# rld-node.net
KiCad netlist of a schematic drawn in EAGLE
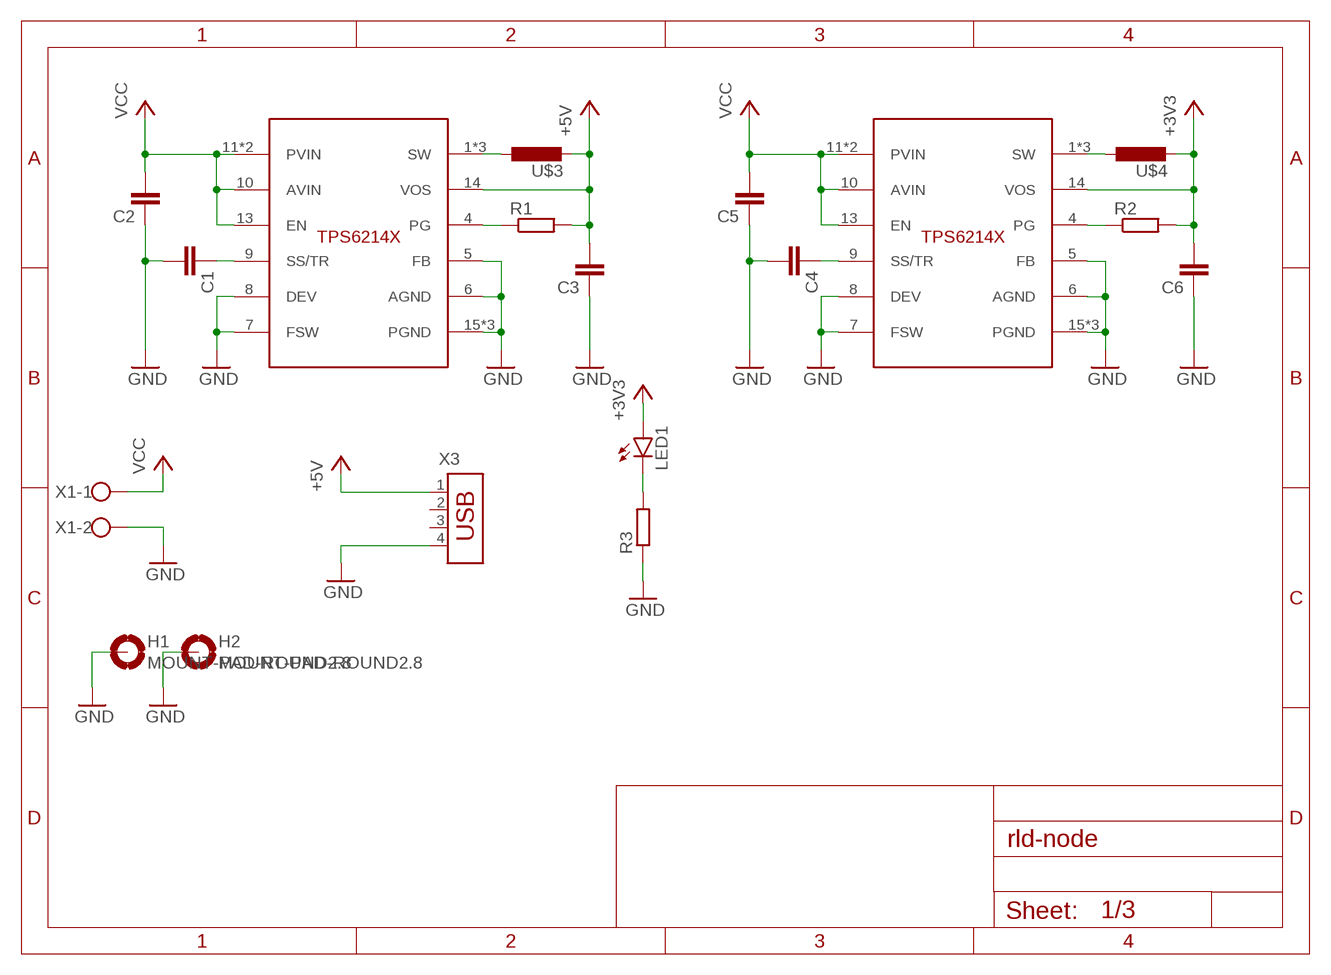
[diagram p0: schematic, sheet 1]
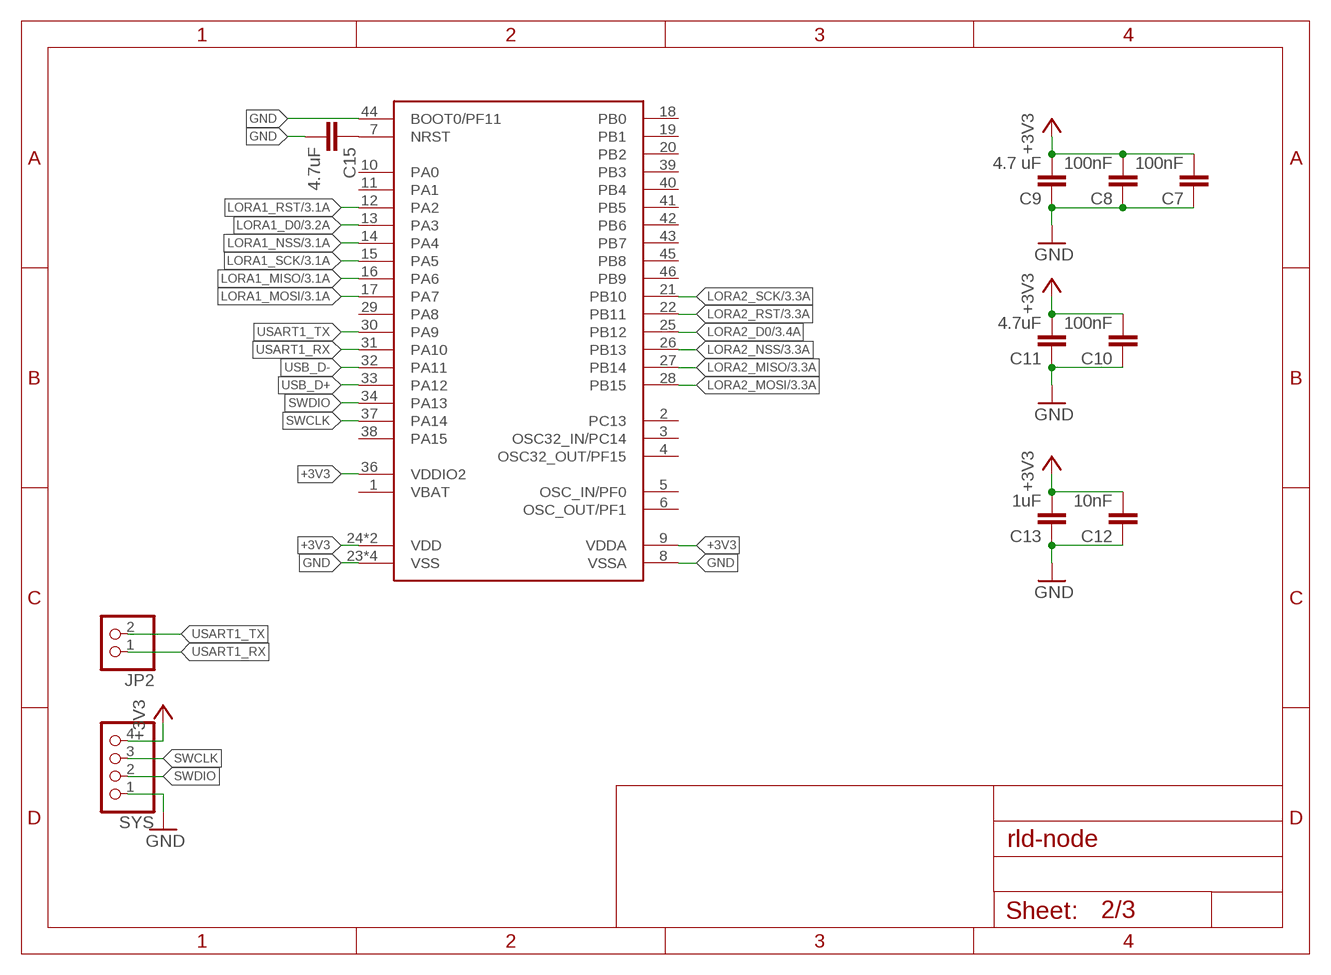
[diagram p1: schematic, sheet 2]
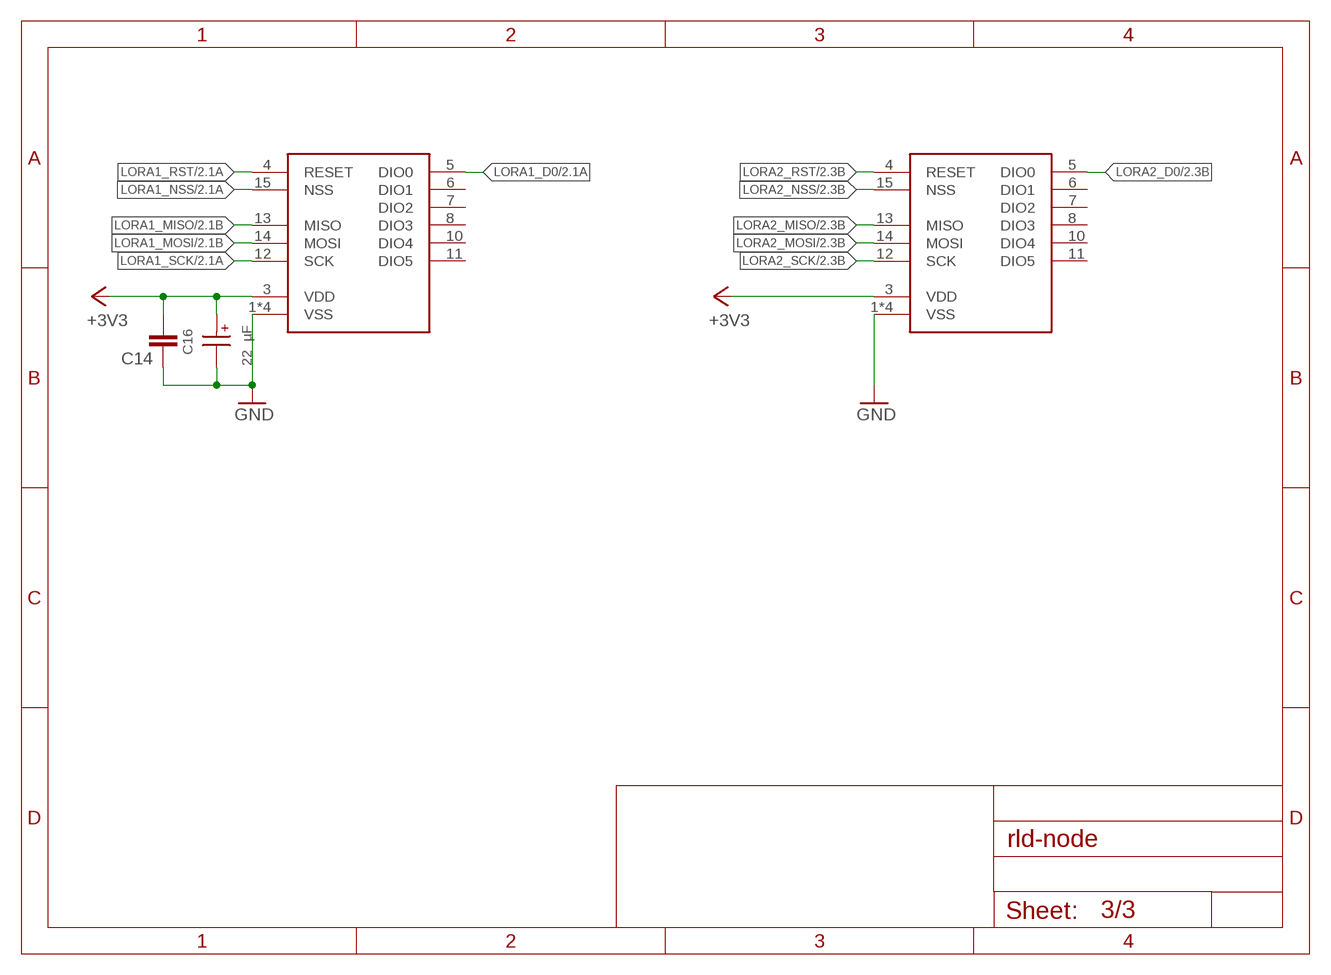
[diagram p2: schematic, sheet 3]

(export (version "E")
  (design (tool "Eeschema 10.0.6"))
  (components
    (comp (ref "C1")
      (value "C-EUC0805")
      (footprint "eagle-import:C0805")
      (libsource (lib "eagle-import") (part "C-EUC0805"))
    )
    (comp (ref "C2")
      (value "C-EUC0805")
      (footprint "eagle-import:C0805")
      (libsource (lib "eagle-import") (part "C-EUC0805"))
    )
    (comp (ref "C3")
      (value "C-EUC0805")
      (footprint "eagle-import:C0805")
      (libsource (lib "eagle-import") (part "C-EUC0805"))
    )
    (comp (ref "C4")
      (value "C-EUC0805")
      (footprint "eagle-import:C0805")
      (libsource (lib "eagle-import") (part "C-EUC0805"))
    )
    (comp (ref "C5")
      (value "C-EUC0805")
      (footprint "eagle-import:C0805")
      (libsource (lib "eagle-import") (part "C-EUC0805"))
    )
    (comp (ref "C6")
      (value "C-EUC0805")
      (footprint "eagle-import:C0805")
      (libsource (lib "eagle-import") (part "C-EUC0805"))
    )
    (comp (ref "H1")
      (value "MOUNT-PAD-ROUND2.8")
      (footprint "eagle-import:2,8-PAD")
      (libsource (lib "eagle-import") (part "MOUNT-PAD-ROUND2.8"))
    )
    (comp (ref "H2")
      (value "MOUNT-PAD-ROUND2.8")
      (footprint "eagle-import:2,8-PAD")
      (libsource (lib "eagle-import") (part "MOUNT-PAD-ROUND2.8"))
    )
    (comp (ref "L1")
      (value "TPS6214X")
      (footprint "eagle-import:VQFN16-3X3")
      (libsource (lib "eagle-import") (part "TPS6214X"))
    )
    (comp (ref "L2")
      (value "TPS6214X")
      (footprint "eagle-import:VQFN16-3X3")
      (libsource (lib "eagle-import") (part "TPS6214X"))
    )
    (comp (ref "LED1")
      (value "LEDSML0805")
      (footprint "eagle-import:SML0805")
      (libsource (lib "eagle-import") (part "LEDSML0805"))
    )
    (comp (ref "R1")
      (value "R-EU_R0805")
      (footprint "eagle-import:R0805")
      (libsource (lib "eagle-import") (part "R-EU_R0805"))
    )
    (comp (ref "R2")
      (value "R-EU_R0805")
      (footprint "eagle-import:R0805")
      (libsource (lib "eagle-import") (part "R-EU_R0805"))
    )
    (comp (ref "R3")
      (value "R-EU_R0805")
      (footprint "eagle-import:R0805")
      (libsource (lib "eagle-import") (part "R-EU_R0805"))
    )
    (comp (ref "U$3")
      (value "IHLP-1212")
      (footprint "eagle-import:1212BZ")
      (libsource (lib "eagle-import") (part "IHLP-1212"))
    )
    (comp (ref "U$4")
      (value "IHLP-1212")
      (footprint "eagle-import:1212BZ")
      (libsource (lib "eagle-import") (part "IHLP-1212"))
    )
    (comp (ref "X1")
      (value "W237-102")
      (footprint "eagle-import:W237-102")
      (fields (field (name "MPN") "237-102"))
      (libsource (lib "eagle-import") (part "W237-102"))
    )
    (comp (ref "X3")
      (value "USB-787616")
      (footprint "eagle-import:USB")
      (libsource (lib "eagle-import") (part "USB-787616"))
    )
    (comp (ref "C7")
      (value "100nF")
      (footprint "eagle-import:C0805")
      (libsource (lib "eagle-import") (part "C-EUC0805"))
    )
    (comp (ref "C8")
      (value "100nF")
      (footprint "eagle-import:C0805")
      (libsource (lib "eagle-import") (part "C-EUC0805"))
    )
    (comp (ref "C9")
      (value "4.7 uF")
      (footprint "eagle-import:C0805")
      (libsource (lib "eagle-import") (part "C-EUC0805"))
    )
    (comp (ref "C10")
      (value "100nF")
      (footprint "eagle-import:C0805")
      (libsource (lib "eagle-import") (part "C-EUC0805"))
    )
    (comp (ref "C11")
      (value "4.7uF")
      (footprint "eagle-import:C0805")
      (libsource (lib "eagle-import") (part "C-EUC0805"))
    )
    (comp (ref "C12")
      (value "10nF")
      (footprint "eagle-import:C0805")
      (libsource (lib "eagle-import") (part "C-EUC0805"))
    )
    (comp (ref "C13")
      (value "1uF")
      (footprint "eagle-import:C0805")
      (libsource (lib "eagle-import") (part "C-EUC0805"))
    )
    (comp (ref "C15")
      (value "4.7uF")
      (footprint "eagle-import:C0805")
      (libsource (lib "eagle-import") (part "C-EUC0805"))
    )
    (comp (ref "JP2")
      (value "PINHD-1X2")
      (footprint "eagle-import:1X02")
      (libsource (lib "eagle-import") (part "PINHD-1X2"))
    )
    (comp (ref "SYS")
      (value "PINHD-1X4")
      (footprint "eagle-import:1X04")
      (libsource (lib "eagle-import") (part "PINHD-1X4"))
    )
    (comp (ref "U$5")
      (value "STM32-F042X4/6-48")
      (footprint "eagle-import:UFQFPN48-7X7")
      (libsource (lib "eagle-import") (part "STM32-F042X4/6-48"))
    )
    (comp (ref "C14")
      (value "C-EUC0805")
      (footprint "eagle-import:C0805")
      (libsource (lib "eagle-import") (part "C-EUC0805"))
    )
    (comp (ref "C16")
      (value "22 µF")
      (footprint "eagle-import:WCAP-ASLI_4X5.5(DXL)")
      (libsource (lib "eagle-import") (part "WCAP-ASLI_4X5.5_865080340003"))
    )
    (comp (ref "U$6")
      (value "RA-02")
      (footprint "eagle-import:RA-01_RA-02")
      (libsource (lib "eagle-import") (part "RA-02"))
    )
    (comp (ref "U$7")
      (value "RA-02")
      (footprint "eagle-import:RA-01_RA-02")
      (libsource (lib "eagle-import") (part "RA-02"))
    )
  )
  (nets
    (net (code "1") (name "+3V3") (class "Default")
      (node (ref "C10") (pin "2") (pinfunction "2_2") (pintype "passive"))
      (node (ref "C11") (pin "2") (pinfunction "2_2") (pintype "passive"))
      (node (ref "C12") (pin "2") (pinfunction "2_2") (pintype "passive"))
      (node (ref "C13") (pin "2") (pinfunction "2_2") (pintype "passive"))
      (node (ref "C14") (pin "2") (pinfunction "2_2") (pintype "passive"))
      (node (ref "C16") (pin "1") (pinfunction "+_1") (pintype "passive"))
      (node (ref "C6") (pin "2") (pinfunction "2_2") (pintype "passive"))
      (node (ref "C7") (pin "2") (pinfunction "2_2") (pintype "passive"))
      (node (ref "C8") (pin "2") (pinfunction "2_2") (pintype "passive"))
      (node (ref "C9") (pin "2") (pinfunction "2_2") (pintype "passive"))
      (node (ref "L2") (pin "14") (pinfunction "VOS_14") (pintype "bidirectional"))
      (node (ref "LED1") (pin "A") (pinfunction "A_A") (pintype "passive"))
      (node (ref "R2") (pin "2") (pinfunction "2_2") (pintype "passive"))
      (node (ref "SYS") (pin "4") (pinfunction "4_4") (pintype "passive"))
      (node (ref "U$4") (pin "2") (pinfunction "2_2") (pintype "passive"))
      (node (ref "U$5") (pin "24") (pinfunction "VDD_24") (pintype "bidirectional"))
      (node (ref "U$5") (pin "36") (pinfunction "VDDIO2_36") (pintype "bidirectional"))
      (node (ref "U$5") (pin "48") (pinfunction "VDD_48") (pintype "bidirectional"))
      (node (ref "U$5") (pin "9") (pinfunction "VDDA_9") (pintype "bidirectional"))
      (node (ref "U$6") (pin "3") (pinfunction "VDD_3") (pintype "bidirectional"))
      (node (ref "U$7") (pin "3") (pinfunction "VDD_3") (pintype "bidirectional"))
    )
    (net (code "2") (name "+5V") (class "Default")
      (node (ref "C3") (pin "2") (pinfunction "2_2") (pintype "passive"))
      (node (ref "L1") (pin "14") (pinfunction "VOS_14") (pintype "bidirectional"))
      (node (ref "R1") (pin "2") (pinfunction "2_2") (pintype "passive"))
      (node (ref "U$3") (pin "2") (pinfunction "2_2") (pintype "passive"))
      (node (ref "X3") (pin "1") (pinfunction "1_1") (pintype "passive"))
    )
    (net (code "3") (name "GND") (class "Default")
      (node (ref "C1") (pin "2") (pinfunction "2_2") (pintype "passive"))
      (node (ref "C10") (pin "1") (pinfunction "1_1") (pintype "passive"))
      (node (ref "C11") (pin "1") (pinfunction "1_1") (pintype "passive"))
      (node (ref "C12") (pin "1") (pinfunction "1_1") (pintype "passive"))
      (node (ref "C13") (pin "1") (pinfunction "1_1") (pintype "passive"))
      (node (ref "C14") (pin "1") (pinfunction "1_1") (pintype "passive"))
      (node (ref "C15") (pin "2") (pinfunction "2_2") (pintype "passive"))
      (node (ref "C16") (pin "2") (pinfunction "-_2") (pintype "passive"))
      (node (ref "C2") (pin "1") (pinfunction "1_1") (pintype "passive"))
      (node (ref "C3") (pin "1") (pinfunction "1_1") (pintype "passive"))
      (node (ref "C4") (pin "2") (pinfunction "2_2") (pintype "passive"))
      (node (ref "C5") (pin "1") (pinfunction "1_1") (pintype "passive"))
      (node (ref "C6") (pin "1") (pinfunction "1_1") (pintype "passive"))
      (node (ref "C7") (pin "1") (pinfunction "1_1") (pintype "passive"))
      (node (ref "C8") (pin "1") (pinfunction "1_1") (pintype "passive"))
      (node (ref "C9") (pin "1") (pinfunction "1_1") (pintype "passive"))
      (node (ref "H1") (pin "B2,8") (pinfunction "MOUNT_B2,8") (pintype "passive"))
      (node (ref "H2") (pin "B2,8") (pinfunction "MOUNT_B2,8") (pintype "passive"))
      (node (ref "L1") (pin "15") (pinfunction "PGND_15") (pintype "bidirectional"))
      (node (ref "L1") (pin "16") (pinfunction "PGND_16") (pintype "bidirectional"))
      (node (ref "L1") (pin "17") (pinfunction "PGND_17") (pintype "bidirectional"))
      (node (ref "L1") (pin "5") (pinfunction "FB_5") (pintype "bidirectional"))
      (node (ref "L1") (pin "6") (pinfunction "AGND_6") (pintype "bidirectional"))
      (node (ref "L1") (pin "7") (pinfunction "FSW_7") (pintype "bidirectional"))
      (node (ref "L1") (pin "8") (pinfunction "DEV_8") (pintype "bidirectional"))
      (node (ref "L2") (pin "15") (pinfunction "PGND_15") (pintype "bidirectional"))
      (node (ref "L2") (pin "16") (pinfunction "PGND_16") (pintype "bidirectional"))
      (node (ref "L2") (pin "17") (pinfunction "PGND_17") (pintype "bidirectional"))
      (node (ref "L2") (pin "5") (pinfunction "FB_5") (pintype "bidirectional"))
      (node (ref "L2") (pin "6") (pinfunction "AGND_6") (pintype "bidirectional"))
      (node (ref "L2") (pin "7") (pinfunction "FSW_7") (pintype "bidirectional"))
      (node (ref "L2") (pin "8") (pinfunction "DEV_8") (pintype "bidirectional"))
      (node (ref "R3") (pin "1") (pinfunction "1_1") (pintype "passive"))
      (node (ref "SYS") (pin "1") (pinfunction "1_1") (pintype "passive"))
      (node (ref "U$5") (pin "23") (pinfunction "VSS_23") (pintype "bidirectional"))
      (node (ref "U$5") (pin "35") (pinfunction "VSS_35") (pintype "bidirectional"))
      (node (ref "U$5") (pin "44") (pinfunction "BOOT0/PF11_44") (pintype "bidirectional"))
      (node (ref "U$5") (pin "47") (pinfunction "VSS_47") (pintype "bidirectional"))
      (node (ref "U$5") (pin "49") (pinfunction "VSS_49") (pintype "bidirectional"))
      (node (ref "U$5") (pin "8") (pinfunction "VSSA_8") (pintype "bidirectional"))
      (node (ref "U$6") (pin "1") (pinfunction "VSS_1") (pintype "bidirectional"))
      (node (ref "U$6") (pin "16") (pinfunction "VSS_16") (pintype "bidirectional"))
      (node (ref "U$6") (pin "2") (pinfunction "VSS_2") (pintype "bidirectional"))
      (node (ref "U$6") (pin "9") (pinfunction "VSS_9") (pintype "bidirectional"))
      (node (ref "U$7") (pin "1") (pinfunction "VSS_1") (pintype "bidirectional"))
      (node (ref "U$7") (pin "16") (pinfunction "VSS_16") (pintype "bidirectional"))
      (node (ref "U$7") (pin "2") (pinfunction "VSS_2") (pintype "bidirectional"))
      (node (ref "U$7") (pin "9") (pinfunction "VSS_9") (pintype "bidirectional"))
      (node (ref "X1") (pin "2") (pinfunction "KL_2") (pintype "passive"))
      (node (ref "X3") (pin "4") (pinfunction "4_4") (pintype "passive"))
    )
    (net (code "4") (name "LORA1_D0") (class "Default")
      (node (ref "U$5") (pin "13") (pinfunction "PA3_13") (pintype "bidirectional"))
      (node (ref "U$6") (pin "5") (pinfunction "DIO0_5") (pintype "bidirectional"))
    )
    (net (code "5") (name "LORA1_MISO") (class "Default")
      (node (ref "U$5") (pin "16") (pinfunction "PA6_16") (pintype "bidirectional"))
      (node (ref "U$6") (pin "13") (pinfunction "MISO_13") (pintype "bidirectional"))
    )
    (net (code "6") (name "LORA1_MOSI") (class "Default")
      (node (ref "U$5") (pin "17") (pinfunction "PA7_17") (pintype "bidirectional"))
      (node (ref "U$6") (pin "14") (pinfunction "MOSI_14") (pintype "bidirectional"))
    )
    (net (code "7") (name "LORA1_NSS") (class "Default")
      (node (ref "U$5") (pin "14") (pinfunction "PA4_14") (pintype "bidirectional"))
      (node (ref "U$6") (pin "15") (pinfunction "NSS_15") (pintype "bidirectional"))
    )
    (net (code "8") (name "LORA1_RST") (class "Default")
      (node (ref "U$5") (pin "12") (pinfunction "PA2_12") (pintype "bidirectional"))
      (node (ref "U$6") (pin "4") (pinfunction "RESET_4") (pintype "bidirectional"))
    )
    (net (code "9") (name "LORA1_SCK") (class "Default")
      (node (ref "U$5") (pin "15") (pinfunction "PA5_15") (pintype "bidirectional"))
      (node (ref "U$6") (pin "12") (pinfunction "SCK_12") (pintype "bidirectional"))
    )
    (net (code "10") (name "LORA2_D0") (class "Default")
      (node (ref "U$5") (pin "25") (pinfunction "PB12_25") (pintype "bidirectional"))
      (node (ref "U$7") (pin "5") (pinfunction "DIO0_5") (pintype "bidirectional"))
    )
    (net (code "11") (name "LORA2_MISO") (class "Default")
      (node (ref "U$5") (pin "27") (pinfunction "PB14_27") (pintype "bidirectional"))
      (node (ref "U$7") (pin "13") (pinfunction "MISO_13") (pintype "bidirectional"))
    )
    (net (code "12") (name "LORA2_MOSI") (class "Default")
      (node (ref "U$5") (pin "28") (pinfunction "PB15_28") (pintype "bidirectional"))
      (node (ref "U$7") (pin "14") (pinfunction "MOSI_14") (pintype "bidirectional"))
    )
    (net (code "13") (name "LORA2_NSS") (class "Default")
      (node (ref "U$5") (pin "26") (pinfunction "PB13_26") (pintype "bidirectional"))
      (node (ref "U$7") (pin "15") (pinfunction "NSS_15") (pintype "bidirectional"))
    )
    (net (code "14") (name "LORA2_RST") (class "Default")
      (node (ref "U$5") (pin "22") (pinfunction "PB11_22") (pintype "bidirectional"))
      (node (ref "U$7") (pin "4") (pinfunction "RESET_4") (pintype "bidirectional"))
    )
    (net (code "15") (name "LORA2_SCK") (class "Default")
      (node (ref "U$5") (pin "21") (pinfunction "PB10_21") (pintype "bidirectional"))
      (node (ref "U$7") (pin "12") (pinfunction "SCK_12") (pintype "bidirectional"))
    )
    (net (code "16") (name "Net-(L1-PG)") (class "Default")
      (node (ref "L1") (pin "4") (pinfunction "PG_4") (pintype "bidirectional"))
      (node (ref "R1") (pin "1") (pinfunction "1_1") (pintype "passive"))
    )
    (net (code "17") (name "Net-(L1-SS{slash}TR)") (class "Default")
      (node (ref "C1") (pin "1") (pinfunction "1_1") (pintype "passive"))
      (node (ref "L1") (pin "9") (pinfunction "SS/TR_9") (pintype "bidirectional"))
    )
    (net (code "18") (name "Net-(L1-SW-Pad1)") (class "Default")
      (node (ref "L1") (pin "1") (pinfunction "SW_1") (pintype "bidirectional"))
      (node (ref "L1") (pin "2") (pinfunction "SW_2") (pintype "bidirectional"))
      (node (ref "L1") (pin "3") (pinfunction "SW_3") (pintype "bidirectional"))
      (node (ref "U$3") (pin "1") (pinfunction "1_1") (pintype "passive"))
    )
    (net (code "19") (name "Net-(L2-PG)") (class "Default")
      (node (ref "L2") (pin "4") (pinfunction "PG_4") (pintype "bidirectional"))
      (node (ref "R2") (pin "1") (pinfunction "1_1") (pintype "passive"))
    )
    (net (code "20") (name "Net-(L2-SS{slash}TR)") (class "Default")
      (node (ref "C4") (pin "1") (pinfunction "1_1") (pintype "passive"))
      (node (ref "L2") (pin "9") (pinfunction "SS/TR_9") (pintype "bidirectional"))
    )
    (net (code "21") (name "Net-(L2-SW-Pad1)") (class "Default")
      (node (ref "L2") (pin "1") (pinfunction "SW_1") (pintype "bidirectional"))
      (node (ref "L2") (pin "2") (pinfunction "SW_2") (pintype "bidirectional"))
      (node (ref "L2") (pin "3") (pinfunction "SW_3") (pintype "bidirectional"))
      (node (ref "U$4") (pin "1") (pinfunction "1_1") (pintype "passive"))
    )
    (net (code "22") (name "Net-(LED1-PadC)") (class "Default")
      (node (ref "LED1") (pin "C") (pinfunction "C_C") (pintype "passive"))
      (node (ref "R3") (pin "2") (pinfunction "2_2") (pintype "passive"))
    )
    (net (code "23") (name "Net-(U$5-NRST)") (class "Default")
      (node (ref "C15") (pin "1") (pinfunction "1_1") (pintype "passive"))
      (node (ref "U$5") (pin "7") (pinfunction "NRST_7") (pintype "bidirectional"))
    )
    (net (code "24") (name "SWCLK") (class "Default")
      (node (ref "SYS") (pin "3") (pinfunction "3_3") (pintype "passive"))
      (node (ref "U$5") (pin "37") (pinfunction "PA14_37") (pintype "bidirectional"))
    )
    (net (code "25") (name "SWDIO") (class "Default")
      (node (ref "SYS") (pin "2") (pinfunction "2_2") (pintype "passive"))
      (node (ref "U$5") (pin "34") (pinfunction "PA13_34") (pintype "bidirectional"))
    )
    (net (code "26") (name "USART1_RX") (class "Default")
      (node (ref "JP2") (pin "1") (pinfunction "1_1") (pintype "passive"))
      (node (ref "U$5") (pin "31") (pinfunction "PA10_31") (pintype "bidirectional"))
    )
    (net (code "27") (name "USART1_TX") (class "Default")
      (node (ref "JP2") (pin "2") (pinfunction "2_2") (pintype "passive"))
      (node (ref "U$5") (pin "30") (pinfunction "PA9_30") (pintype "bidirectional"))
    )
    (net (code "28") (name "USB_D+") (class "Default")
      (node (ref "U$5") (pin "33") (pinfunction "PA12_33") (pintype "bidirectional"))
    )
    (net (code "29") (name "USB_D-") (class "Default")
      (node (ref "U$5") (pin "32") (pinfunction "PA11_32") (pintype "bidirectional"))
    )
    (net (code "30") (name "VCC") (class "Default")
      (node (ref "C2") (pin "2") (pinfunction "2_2") (pintype "passive"))
      (node (ref "C5") (pin "2") (pinfunction "2_2") (pintype "passive"))
      (node (ref "L1") (pin "10") (pinfunction "AVIN_10") (pintype "bidirectional"))
      (node (ref "L1") (pin "11") (pinfunction "PVIN_11") (pintype "bidirectional"))
      (node (ref "L1") (pin "12") (pinfunction "PVIN_12") (pintype "bidirectional"))
      (node (ref "L1") (pin "13") (pinfunction "EN_13") (pintype "bidirectional"))
      (node (ref "L2") (pin "10") (pinfunction "AVIN_10") (pintype "bidirectional"))
      (node (ref "L2") (pin "11") (pinfunction "PVIN_11") (pintype "bidirectional"))
      (node (ref "L2") (pin "12") (pinfunction "PVIN_12") (pintype "bidirectional"))
      (node (ref "L2") (pin "13") (pinfunction "EN_13") (pintype "bidirectional"))
      (node (ref "X1") (pin "1") (pinfunction "KL_1") (pintype "passive"))
    )
    (net (code "31") (name "unconnected-(U$5-OSC32_IN{slash}PC14-Pad3)") (class "Default")
      (node (ref "U$5") (pin "3") (pinfunction "OSC32_IN/PC14_3") (pintype "bidirectional"))
    )
    (net (code "32") (name "unconnected-(U$5-OSC32_OUT{slash}PF15-Pad4)") (class "Default")
      (node (ref "U$5") (pin "4") (pinfunction "OSC32_OUT/PF15_4") (pintype "bidirectional"))
    )
    (net (code "33") (name "unconnected-(U$5-OSC_IN{slash}PF0-Pad5)") (class "Default")
      (node (ref "U$5") (pin "5") (pinfunction "OSC_IN/PF0_5") (pintype "bidirectional"))
    )
    (net (code "34") (name "unconnected-(U$5-OSC_OUT{slash}PF1-Pad6)") (class "Default")
      (node (ref "U$5") (pin "6") (pinfunction "OSC_OUT/PF1_6") (pintype "bidirectional"))
    )
    (net (code "35") (name "unconnected-(U$5-PA0-Pad10)") (class "Default")
      (node (ref "U$5") (pin "10") (pinfunction "PA0_10") (pintype "bidirectional"))
    )
    (net (code "36") (name "unconnected-(U$5-PA1-Pad11)") (class "Default")
      (node (ref "U$5") (pin "11") (pinfunction "PA1_11") (pintype "bidirectional"))
    )
    (net (code "37") (name "unconnected-(U$5-PA8-Pad29)") (class "Default")
      (node (ref "U$5") (pin "29") (pinfunction "PA8_29") (pintype "bidirectional"))
    )
    (net (code "38") (name "unconnected-(U$5-PA15-Pad38)") (class "Default")
      (node (ref "U$5") (pin "38") (pinfunction "PA15_38") (pintype "bidirectional"))
    )
    (net (code "39") (name "unconnected-(U$5-PB0-Pad18)") (class "Default")
      (node (ref "U$5") (pin "18") (pinfunction "PB0_18") (pintype "bidirectional"))
    )
    (net (code "40") (name "unconnected-(U$5-PB1-Pad19)") (class "Default")
      (node (ref "U$5") (pin "19") (pinfunction "PB1_19") (pintype "bidirectional"))
    )
    (net (code "41") (name "unconnected-(U$5-PB2-Pad20)") (class "Default")
      (node (ref "U$5") (pin "20") (pinfunction "PB2_20") (pintype "bidirectional"))
    )
    (net (code "42") (name "unconnected-(U$5-PB3-Pad39)") (class "Default")
      (node (ref "U$5") (pin "39") (pinfunction "PB3_39") (pintype "bidirectional"))
    )
    (net (code "43") (name "unconnected-(U$5-PB4-Pad40)") (class "Default")
      (node (ref "U$5") (pin "40") (pinfunction "PB4_40") (pintype "bidirectional"))
    )
    (net (code "44") (name "unconnected-(U$5-PB5-Pad41)") (class "Default")
      (node (ref "U$5") (pin "41") (pinfunction "PB5_41") (pintype "bidirectional"))
    )
    (net (code "45") (name "unconnected-(U$5-PB6-Pad42)") (class "Default")
      (node (ref "U$5") (pin "42") (pinfunction "PB6_42") (pintype "bidirectional"))
    )
    (net (code "46") (name "unconnected-(U$5-PB7-Pad43)") (class "Default")
      (node (ref "U$5") (pin "43") (pinfunction "PB7_43") (pintype "bidirectional"))
    )
    (net (code "47") (name "unconnected-(U$5-PB8-Pad45)") (class "Default")
      (node (ref "U$5") (pin "45") (pinfunction "PB8_45") (pintype "bidirectional"))
    )
    (net (code "48") (name "unconnected-(U$5-PB9-Pad46)") (class "Default")
      (node (ref "U$5") (pin "46") (pinfunction "PB9_46") (pintype "bidirectional"))
    )
    (net (code "49") (name "unconnected-(U$5-PC13-Pad2)") (class "Default")
      (node (ref "U$5") (pin "2") (pinfunction "PC13_2") (pintype "bidirectional"))
    )
    (net (code "50") (name "unconnected-(U$5-VBAT-Pad1)") (class "Default")
      (node (ref "U$5") (pin "1") (pinfunction "VBAT_1") (pintype "bidirectional"))
    )
    (net (code "51") (name "unconnected-(U$6-DIO1-Pad6)") (class "Default")
      (node (ref "U$6") (pin "6") (pinfunction "DIO1_6") (pintype "bidirectional"))
    )
    (net (code "52") (name "unconnected-(U$6-DIO2-Pad7)") (class "Default")
      (node (ref "U$6") (pin "7") (pinfunction "DIO2_7") (pintype "bidirectional"))
    )
    (net (code "53") (name "unconnected-(U$6-DIO3-Pad8)") (class "Default")
      (node (ref "U$6") (pin "8") (pinfunction "DIO3_8") (pintype "bidirectional"))
    )
    (net (code "54") (name "unconnected-(U$6-DIO4-Pad10)") (class "Default")
      (node (ref "U$6") (pin "10") (pinfunction "DIO4_10") (pintype "bidirectional"))
    )
    (net (code "55") (name "unconnected-(U$6-DIO5-Pad11)") (class "Default")
      (node (ref "U$6") (pin "11") (pinfunction "DIO5_11") (pintype "bidirectional"))
    )
    (net (code "56") (name "unconnected-(U$7-DIO1-Pad6)") (class "Default")
      (node (ref "U$7") (pin "6") (pinfunction "DIO1_6") (pintype "bidirectional"))
    )
    (net (code "57") (name "unconnected-(U$7-DIO2-Pad7)") (class "Default")
      (node (ref "U$7") (pin "7") (pinfunction "DIO2_7") (pintype "bidirectional"))
    )
    (net (code "58") (name "unconnected-(U$7-DIO3-Pad8)") (class "Default")
      (node (ref "U$7") (pin "8") (pinfunction "DIO3_8") (pintype "bidirectional"))
    )
    (net (code "59") (name "unconnected-(U$7-DIO4-Pad10)") (class "Default")
      (node (ref "U$7") (pin "10") (pinfunction "DIO4_10") (pintype "bidirectional"))
    )
    (net (code "60") (name "unconnected-(U$7-DIO5-Pad11)") (class "Default")
      (node (ref "U$7") (pin "11") (pinfunction "DIO5_11") (pintype "bidirectional"))
    )
    (net (code "61") (name "unconnected-(X3-Pad2)") (class "Default")
      (node (ref "X3") (pin "2") (pinfunction "2_2") (pintype "passive"))
    )
    (net (code "62") (name "unconnected-(X3-Pad3)") (class "Default")
      (node (ref "X3") (pin "3") (pinfunction "3_3") (pintype "passive"))
    )
  )
)
